# HIVE_BOARD_WIRELESS.net
KiCad netlist of a schematic drawn in Altium Designer
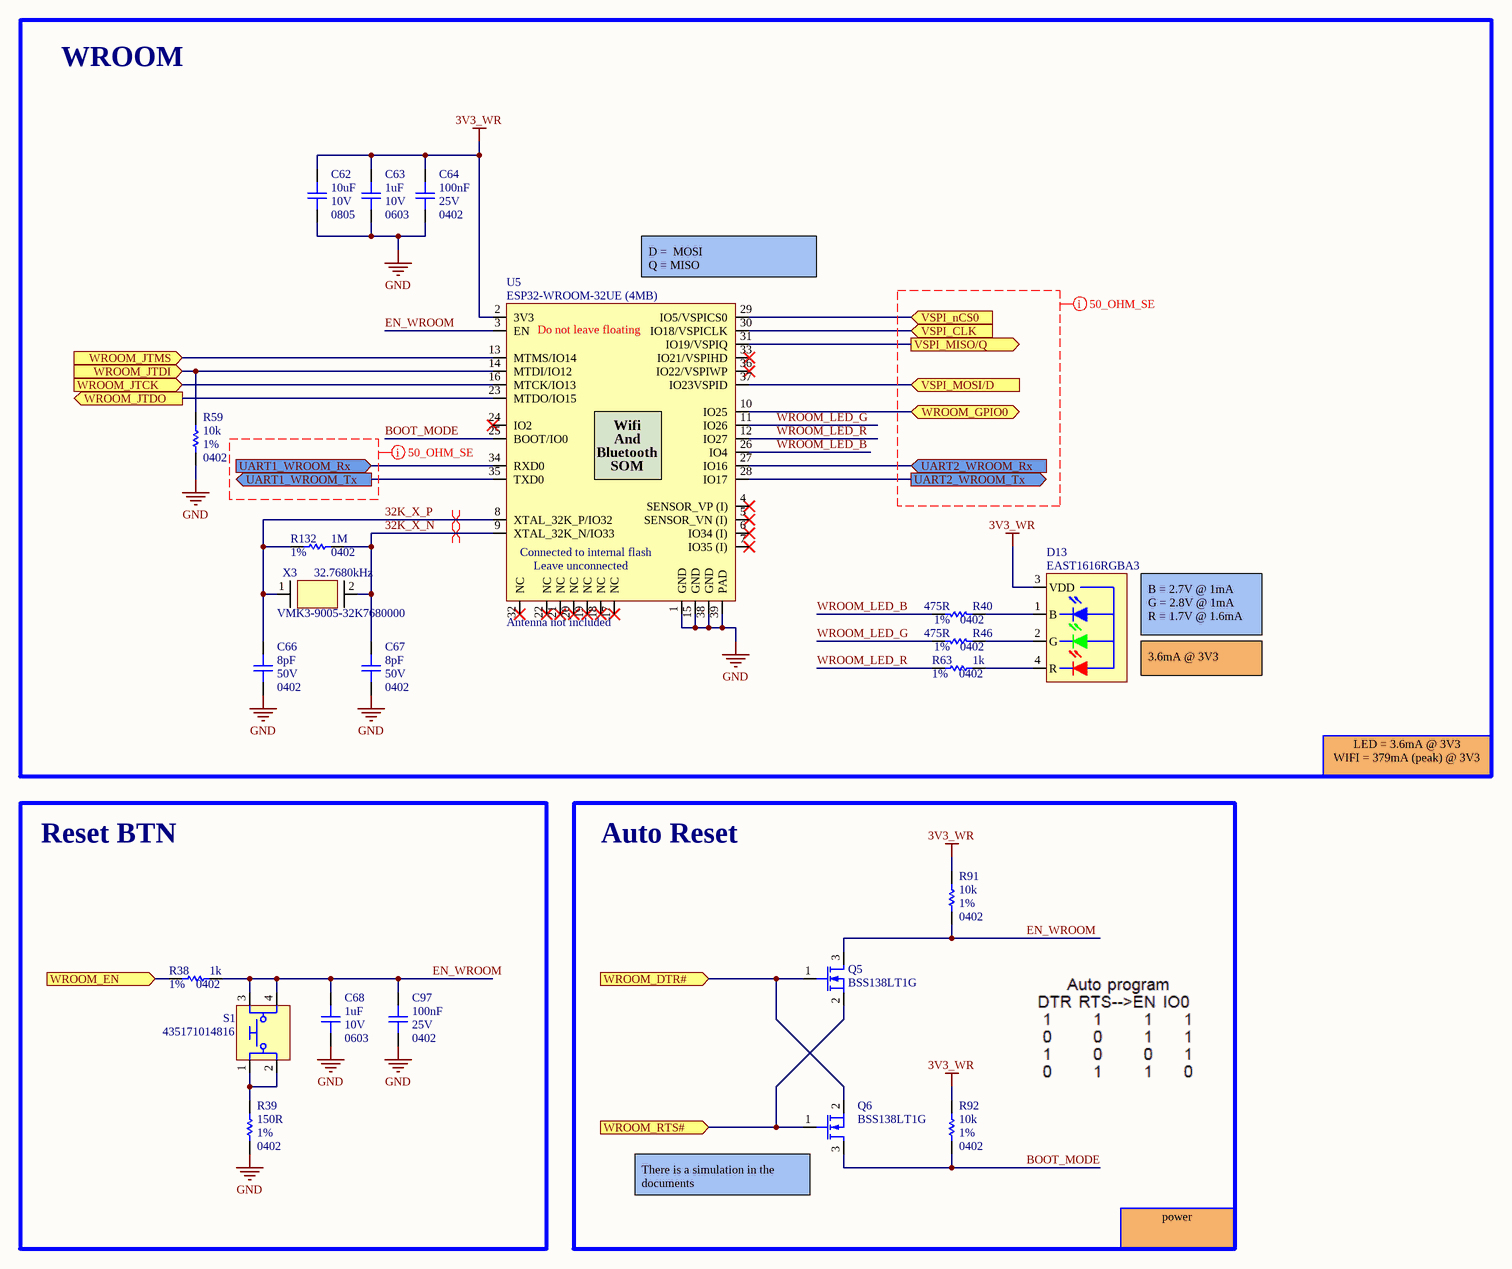
[diagram p0: HIVE_BOARD_WIRELESS.SchDoc]

(export (version "E")
  (design (tool "Eeschema 10.0.6"))
  (components
    (comp (ref "C62")
      (value "10uF")
      (footprint "CAP_CER_0805")
      (description "CAP - CER 10UF 10% 10V X5R - 0805")
      (fields
        (field (name "TOLERANCE") "10%")
        (field (name "PACKAGE") "0805")
        (field (name "VOLTAGE RATING") "10V")
        (field (name "Comment") "LMK212BJ106KG-T")
        (field (name "CREATEDBY/DATE") "Caroline Paulin / 25 juillet 2018")
        (field (name "VERIFIEDBY") "Nicolas V. (2019-01-22)")
      )
      (libsource (lib "GRAMS_MASTER_LIB") (part "CAP_CER_LMK212BJ106KG-T"))
    )
    (comp (ref "C63")
      (value "1uF")
      (footprint "CAP_CER_0603")
      (description "CAP - CER 1uF 10V 10% X5R - 0603")
      (fields
        (field (name "TOLERANCE") "10%")
        (field (name "PACKAGE") "0603")
        (field (name "VOLTAGE RATING") "10V")
        (field (name "Comment") "C0603C105K8PACTU")
        (field (name "CREATEDBY/DATE") "Hubert Dube - 21/07/20")
        (field (name "VERIFIEDBY") "Louis-Daniel Gaulin - 21/07/20")
      )
      (libsource (lib "SWARMUS_LIB") (part "CAP_CER_C0603C105K8PACTU"))
    )
    (comp (ref "C64")
      (value "100nF")
      (footprint "CAP_CER_0402")
      (description "CAP - CER 0.1µF 10% 25V X7R - 0402")
      (fields
        (field (name "TOLERANCE") "10%")
        (field (name "PACKAGE") "0402")
        (field (name "VOLTAGE RATING") "25V")
        (field (name "Comment") "CGA2B3X7R1E104K050BB")
        (field (name "CREATEDBY/DATE") "Nicolas Roy 2018-11-07")
        (field (name "VERIFIEDBY") "Nicolas V. (2019-01-22)")
      )
      (libsource (lib "GRAMS_MASTER_LIB") (part "CAP_CER_CGA2B3X7R1E104K050BB"))
    )
    (comp (ref "C66")
      (value "8pF")
      (footprint "CAP_CER_0402")
      (description "CAP - CER 8PF 50V C0G/NP0 - 0402")
      (fields
        (field (name "TOLERANCE") "±0.5pF")
        (field (name "PACKAGE") "0402")
        (field (name "VOLTAGE RATING") "50V")
        (field (name "Comment") "CC0402DRNPO9BN8R0")
        (field (name "CREATEDBY/DATE") "Hubert Dube - 04/10/20")
        (field (name "VERIFIEDBY") "Louis-Daniel Gaulin - 09/11/2020")
      )
      (libsource (lib "SWARMUS_LIB") (part "CAP_CER_CC0402DRNPO9BN8R0"))
    )
    (comp (ref "C67")
      (value "8pF")
      (footprint "CAP_CER_0402")
      (description "CAP - CER 8PF 50V C0G/NP0 - 0402")
      (fields
        (field (name "TOLERANCE") "±0.5pF")
        (field (name "PACKAGE") "0402")
        (field (name "VOLTAGE RATING") "50V")
        (field (name "Comment") "CC0402DRNPO9BN8R0")
        (field (name "CREATEDBY/DATE") "Hubert Dube - 04/10/20")
        (field (name "VERIFIEDBY") "Louis-Daniel Gaulin - 09/11/2020")
      )
      (libsource (lib "SWARMUS_LIB") (part "CAP_CER_CC0402DRNPO9BN8R0"))
    )
    (comp (ref "C68")
      (value "1uF")
      (footprint "CAP_CER_0603")
      (description "CAP - CER 1uF 10V 10% X5R - 0603")
      (fields
        (field (name "TOLERANCE") "10%")
        (field (name "PACKAGE") "0603")
        (field (name "VOLTAGE RATING") "10V")
        (field (name "Comment") "C0603C105K8PACTU")
        (field (name "CREATEDBY/DATE") "Hubert Dube - 21/07/20")
        (field (name "VERIFIEDBY") "Louis-Daniel Gaulin - 21/07/20")
      )
      (libsource (lib "SWARMUS_LIB") (part "CAP_CER_C0603C105K8PACTU"))
    )
    (comp (ref "C97")
      (value "100nF")
      (footprint "CAP_CER_0402")
      (description "CAP - CER 0.1µF 10% 25V X7R - 0402")
      (fields
        (field (name "TOLERANCE") "10%")
        (field (name "PACKAGE") "0402")
        (field (name "VOLTAGE RATING") "25V")
        (field (name "Comment") "CGA2B3X7R1E104K050BB")
        (field (name "CREATEDBY/DATE") "Nicolas Roy 2018-11-07")
        (field (name "VERIFIEDBY") "Nicolas V. (2019-01-22)")
      )
      (libsource (lib "GRAMS_MASTER_LIB") (part "CAP_CER_CGA2B3X7R1E104K050BB"))
    )
    (comp (ref "D13")
      (value "EAST1616RGBA3")
      (footprint "DIO_EAST1616RGBA3")
      (fields
        (field (name "TOLERANCE") "±50ppm")
        (field (name "CREATEDBY/DATE") "Hubert Dube - 26/02/2021")
        (field (name "VERIFIEDBY") "PA + Hubert Dube - 19/03/2021")
      )
      (libsource (lib "SWARMUS_LIB") (part "DIO_EAST1616RGBA3"))
    )
    (comp (ref "Q5")
      (value "BSS138LT1G")
      (footprint "TRX_NMOS_BSS138LT1G")
      (description "TRX - NMOS - 50V 200MA - SOT−23-3")
      (fields
        (field (name "CREATEDBY/DATE") "Joel Lemay 2018-06-15")
        (field (name "VERIFIEDBY") "Caroline Paulin - 6 sept 2018")
      )
      (libsource (lib "GRAMS_MASTER_LIB") (part "TRX_NMOS_BSS138LT1G"))
    )
    (comp (ref "Q6")
      (value "BSS138LT1G")
      (footprint "TRX_NMOS_BSS138LT1G")
      (description "TRX - NMOS - 50V 200MA - SOT−23-3")
      (fields
        (field (name "CREATEDBY/DATE") "Joel Lemay 2018-06-15")
        (field (name "VERIFIEDBY") "Caroline Paulin - 6 sept 2018")
      )
      (libsource (lib "GRAMS_MASTER_LIB") (part "TRX_NMOS_BSS138LT1G"))
    )
    (comp (ref "R38")
      (value "1k")
      (footprint "RES_0402")
      (description "RES - 1K OHM 1% 1/16W - 0402")
      (fields
        (field (name "TOLERANCE") "1%")
        (field (name "PACKAGE") "0402")
        (field (name "Comment") "RC0402FR-071KL")
        (field (name "CREATEDBY/DATE") "Jonathan Bouchard 2018-07-05")
        (field (name "VERIFIEDBY") "Arnaud Samson 16-07-18")
      )
      (libsource (lib "GRAMS_MASTER_LIB") (part "RES_RC0402FR-071KL"))
    )
    (comp (ref "R39")
      (value "150R")
      (footprint "RES_0402")
      (description "RES - 150R 1% 1/16W - 0402")
      (fields
        (field (name "TOLERANCE") "1%")
        (field (name "PACKAGE") "0402")
        (field (name "Comment") "RC0402FR-07150RL")
        (field (name "CREATEDBY/DATE") "Jonathan Bouchard 2019-03-25")
        (field (name "VERIFIEDBY") "Nicolas V. (2019-05-02)")
      )
      (libsource (lib "GRAMS_MASTER_LIB") (part "RES_RC0402FR-07150RL"))
    )
    (comp (ref "R40")
      (value "475R")
      (footprint "RES_0402")
      (description "RES - 475R 1% 1/10W- 0402")
      (fields
        (field (name "TOLERANCE") "1%")
        (field (name "PACKAGE") "0402")
        (field (name "Comment") "ERJ-2RKF4750X")
        (field (name "CREATEDBY/DATE") "Keven Deslandes 2018-10-17")
        (field (name "VERIFIEDBY") "Carolilne Paulin - 18/12/2018")
      )
      (libsource (lib "GRAMS_MASTER_LIB") (part "RES_ERJ-2RKF4750X"))
    )
    (comp (ref "R46")
      (value "475R")
      (footprint "RES_0402")
      (description "RES - 475R 1% 1/10W- 0402")
      (fields
        (field (name "TOLERANCE") "1%")
        (field (name "PACKAGE") "0402")
        (field (name "Comment") "ERJ-2RKF4750X")
        (field (name "CREATEDBY/DATE") "Keven Deslandes 2018-10-17")
        (field (name "VERIFIEDBY") "Carolilne Paulin - 18/12/2018")
      )
      (libsource (lib "GRAMS_MASTER_LIB") (part "RES_ERJ-2RKF4750X"))
    )
    (comp (ref "R59")
      (value "10k")
      (footprint "RES_0402")
      (description "RES - 10K OHMS 1% 1/16W - 0402")
      (fields
        (field (name "TOLERANCE") "1%")
        (field (name "PACKAGE") "0402")
        (field (name "Comment") "RC0402FR-0710KL")
        (field (name "CREATEDBY/DATE") "Nicolas V. (2018-11-20)")
        (field (name "VERIFIEDBY") "Nicolas V. (2018-11-20)")
      )
      (libsource (lib "GRAMS_MASTER_LIB") (part "RES_RC0402FR-0710KL"))
    )
    (comp (ref "R63")
      (value "1k")
      (footprint "RES_0402")
      (description "RES - 1K OHM 1% 1/16W - 0402")
      (fields
        (field (name "TOLERANCE") "1%")
        (field (name "PACKAGE") "0402")
        (field (name "Comment") "RC0402FR-071KL")
        (field (name "CREATEDBY/DATE") "Jonathan Bouchard 2018-07-05")
        (field (name "VERIFIEDBY") "Arnaud Samson 16-07-18")
      )
      (libsource (lib "GRAMS_MASTER_LIB") (part "RES_RC0402FR-071KL"))
    )
    (comp (ref "R91")
      (value "10k")
      (footprint "RES_0402")
      (description "RES - 10K OHMS 1% 1/16W - 0402")
      (fields
        (field (name "TOLERANCE") "1%")
        (field (name "PACKAGE") "0402")
        (field (name "Comment") "RC0402FR-0710KL")
        (field (name "CREATEDBY/DATE") "Nicolas V. (2018-11-20)")
        (field (name "VERIFIEDBY") "Nicolas V. (2018-11-20)")
      )
      (libsource (lib "GRAMS_MASTER_LIB") (part "RES_RC0402FR-0710KL"))
    )
    (comp (ref "R92")
      (value "10k")
      (footprint "RES_0402")
      (description "RES - 10K OHMS 1% 1/16W - 0402")
      (fields
        (field (name "TOLERANCE") "1%")
        (field (name "PACKAGE") "0402")
        (field (name "Comment") "RC0402FR-0710KL")
        (field (name "CREATEDBY/DATE") "Nicolas V. (2018-11-20)")
        (field (name "VERIFIEDBY") "Nicolas V. (2018-11-20)")
      )
      (libsource (lib "GRAMS_MASTER_LIB") (part "RES_RC0402FR-0710KL"))
    )
    (comp (ref "R132")
      (value "1M")
      (footprint "RES_0402")
      (description "RES - 1M 1% 1/16W - 0402")
      (fields
        (field (name "TOLERANCE") "1%")
        (field (name "PACKAGE") "0402")
        (field (name "Comment") "RC0402FR-071ML")
        (field (name "CREATEDBY/DATE") "Keven Deslandes 2018-11-09")
        (field (name "VERIFIEDBY") "Caroline Paulin - 7 janv 2019")
      )
      (libsource (lib "GRAMS_MASTER_LIB") (part "RES_RC0402FR-071ML"))
    )
    (comp (ref "S1")
      (value "435171014816")
      (footprint "SWI_TACT_435171014816")
      (description "SWI - SWITCH TACTILE SPST-NO 0.05A 12V -SMD")
      (fields
        (field (name "CREATEDBY/DATE") "Hubert Dube - 22/07/20")
        (field (name "VERIFIEDBY") "Louis-Daniel Gaulin / 12-11-2020")
      )
      (libsource (lib "SWARMUS_LIB") (part "SWI_TACT_435171014816"))
    )
    (comp (ref "U5")
      (value "ESP32-WROOM-32UE (4MB)")
      (footprint "COM_ESP32-WROOM-32UE(8MB)")
      (fields
        (field (name "NOTE") "Antenna not included")
        (field (name "VERIFIEDBY") "Philippe Arsenault/ 2021-03-11")
        (field (name "CREATEDBY/DATE") "Hubert Dube -  25/02/2021")
      )
      (libsource (lib "SWARMUS_LIB") (part "COM_ESP32-WROOM-32UE(4MB)"))
    )
    (comp (ref "X3")
      (value "VMK3-9005-32K7680000")
      (footprint "CRY_VMK3-9005-32K7680000")
      (description "CRY - 32.768KHZ tol:20ppm  - 2-SMD")
      (fields
        (field (name "TOLERANCE") "±20ppm")
        (field (name "ALTIUM_VALUE") "32.7680kHz")
        (field (name "CREATEDBY/DATE") "Louis-Daniel Gaulin / 08-04-2021")
        (field (name "VERIFIEDBY") "Philippe Arsenault/2021-04-15")
      )
      (libsource (lib "SWARMUS_LIB") (part "CRY_VMK3-9005-32K7680000"))
    )
  )
  (nets
    (net (code "1") (name "/32K_X_N") (class "Default")
      (node (ref "C67") (pin "2") (pinfunction "2_2") (pintype "passive"))
      (node (ref "R132") (pin "1") (pinfunction "1_1") (pintype "passive"))
      (node (ref "U5") (pin "9") (pinfunction "XTAL_32K_N/IO33_9") (pintype "passive"))
      (node (ref "X3") (pin "2") (pinfunction "Out/In_2") (pintype "passive"))
    )
    (net (code "2") (name "/32K_X_P") (class "Default")
      (node (ref "C66") (pin "2") (pinfunction "2_2") (pintype "passive"))
      (node (ref "R132") (pin "2") (pinfunction "2_2") (pintype "passive"))
      (node (ref "U5") (pin "8") (pinfunction "XTAL_32K_P/IO32_8") (pintype "passive"))
      (node (ref "X3") (pin "1") (pinfunction "In/Out_1") (pintype "passive"))
    )
    (net (code "3") (name "/BOOT_MODE") (class "Default")
      (node (ref "Q6") (pin "3") (pinfunction "D_3") (pintype "passive"))
      (node (ref "R92") (pin "1") (pinfunction "1_1") (pintype "passive"))
      (node (ref "U5") (pin "25") (pinfunction "BOOT/IO0_25") (pintype "passive"))
    )
    (net (code "4") (name "/EN_WROOM") (class "Default")
      (node (ref "C68") (pin "1") (pinfunction "1_1") (pintype "passive"))
      (node (ref "C97") (pin "2") (pinfunction "2_2") (pintype "passive"))
      (node (ref "Q5") (pin "3") (pinfunction "D_3") (pintype "passive"))
      (node (ref "R38") (pin "1") (pinfunction "1_1") (pintype "passive"))
      (node (ref "R91") (pin "1") (pinfunction "1_1") (pintype "passive"))
      (node (ref "S1") (pin "3") (pinfunction "3_3") (pintype "passive"))
      (node (ref "S1") (pin "4") (pinfunction "4_4") (pintype "passive"))
      (node (ref "U5") (pin "3") (pinfunction "EN_3") (pintype "passive"))
    )
    (net (code "5") (name "/UART1_WROOM_Rx") (class "Default")
      (node (ref "U5") (pin "34") (pinfunction "RXD0_34") (pintype "passive"))
    )
    (net (code "6") (name "/UART1_WROOM_Tx") (class "Default")
      (node (ref "U5") (pin "35") (pinfunction "TXD0_35") (pintype "passive"))
    )
    (net (code "7") (name "/UART2_WROOM_Rx") (class "Default")
      (node (ref "U5") (pin "27") (pinfunction "IO16_27") (pintype "passive"))
    )
    (net (code "8") (name "/UART2_WROOM_Tx") (class "Default")
      (node (ref "U5") (pin "28") (pinfunction "IO17_28") (pintype "passive"))
    )
    (net (code "9") (name "/VSPI_CLK") (class "Default")
      (node (ref "U5") (pin "30") (pinfunction "IO18/VSPICLK_30") (pintype "passive"))
    )
    (net (code "10") (name "/VSPI_MISO{slash}Q") (class "Default")
      (node (ref "U5") (pin "31") (pinfunction "IO19/VSPIQ_31") (pintype "passive"))
    )
    (net (code "11") (name "/VSPI_MOSI{slash}D") (class "Default")
      (node (ref "U5") (pin "37") (pinfunction "IO23VSPID_37") (pintype "passive"))
    )
    (net (code "12") (name "/VSPI_nCS0") (class "Default")
      (node (ref "U5") (pin "29") (pinfunction "IO5/VSPICS0_29") (pintype "passive"))
    )
    (net (code "13") (name "/WROOM_DTR#") (class "Default")
      (node (ref "Q5") (pin "1") (pinfunction "G_1") (pintype "passive"))
      (node (ref "Q6") (pin "2") (pinfunction "S_2") (pintype "passive"))
    )
    (net (code "14") (name "/WROOM_EN") (class "Default")
      (node (ref "R38") (pin "2") (pinfunction "2_2") (pintype "passive"))
    )
    (net (code "15") (name "/WROOM_GPIO0") (class "Default")
      (node (ref "U5") (pin "10") (pinfunction "IO25_10") (pintype "passive"))
    )
    (net (code "16") (name "/WROOM_JTCK") (class "Default")
      (node (ref "U5") (pin "16") (pinfunction "MTCK/IO13_16") (pintype "passive"))
    )
    (net (code "17") (name "/WROOM_JTDI") (class "Default")
      (node (ref "R59") (pin "2") (pinfunction "2_2") (pintype "passive"))
      (node (ref "U5") (pin "14") (pinfunction "MTDI/IO12_14") (pintype "passive"))
    )
    (net (code "18") (name "/WROOM_JTDO") (class "Default")
      (node (ref "U5") (pin "23") (pinfunction "MTDO/IO15_23") (pintype "passive"))
    )
    (net (code "19") (name "/WROOM_JTMS") (class "Default")
      (node (ref "U5") (pin "13") (pinfunction "MTMS/IO14_13") (pintype "passive"))
    )
    (net (code "20") (name "/WROOM_LED_B") (class "Default")
      (node (ref "R40") (pin "2") (pinfunction "2_2") (pintype "passive"))
      (node (ref "U5") (pin "26") (pinfunction "IO4_26") (pintype "passive"))
    )
    (net (code "21") (name "/WROOM_LED_G") (class "Default")
      (node (ref "R46") (pin "2") (pinfunction "2_2") (pintype "passive"))
      (node (ref "U5") (pin "11") (pinfunction "IO26_11") (pintype "passive"))
    )
    (net (code "22") (name "/WROOM_LED_R") (class "Default")
      (node (ref "R63") (pin "2") (pinfunction "2_2") (pintype "passive"))
      (node (ref "U5") (pin "12") (pinfunction "IO27_12") (pintype "passive"))
    )
    (net (code "23") (name "/WROOM_RTS#") (class "Default")
      (node (ref "Q5") (pin "2") (pinfunction "S_2") (pintype "passive"))
      (node (ref "Q6") (pin "1") (pinfunction "G_1") (pintype "passive"))
    )
    (net (code "24") (name "3V3_WR") (class "Default")
      (node (ref "C62") (pin "2") (pinfunction "2_2") (pintype "passive"))
      (node (ref "C63") (pin "1") (pinfunction "1_1") (pintype "passive"))
      (node (ref "C64") (pin "2") (pinfunction "2_2") (pintype "passive"))
      (node (ref "D13") (pin "3") (pinfunction "VDD_3") (pintype "passive"))
      (node (ref "R91") (pin "2") (pinfunction "2_2") (pintype "passive"))
      (node (ref "R92") (pin "2") (pinfunction "2_2") (pintype "passive"))
      (node (ref "U5") (pin "2") (pinfunction "3V3_2") (pintype "passive"))
    )
    (net (code "25") (name "GND") (class "Default")
      (node (ref "C62") (pin "1") (pinfunction "1_1") (pintype "passive"))
      (node (ref "C63") (pin "2") (pinfunction "2_2") (pintype "passive"))
      (node (ref "C64") (pin "1") (pinfunction "1_1") (pintype "passive"))
      (node (ref "C66") (pin "1") (pinfunction "1_1") (pintype "passive"))
      (node (ref "C67") (pin "1") (pinfunction "1_1") (pintype "passive"))
      (node (ref "C68") (pin "2") (pinfunction "2_2") (pintype "passive"))
      (node (ref "C97") (pin "1") (pinfunction "1_1") (pintype "passive"))
      (node (ref "R39") (pin "1") (pinfunction "1_1") (pintype "passive"))
      (node (ref "R59") (pin "1") (pinfunction "1_1") (pintype "passive"))
      (node (ref "U5") (pin "1") (pinfunction "GND_1") (pintype "passive"))
      (node (ref "U5") (pin "15") (pinfunction "GND_15") (pintype "passive"))
      (node (ref "U5") (pin "38") (pinfunction "GND_38") (pintype "passive"))
      (node (ref "U5") (pin "39") (pinfunction "PAD_39") (pintype "passive"))
    )
    (net (code "26") (name "Net-(D13-B)") (class "Default")
      (node (ref "D13") (pin "1") (pinfunction "B_1") (pintype "passive"))
      (node (ref "R40") (pin "1") (pinfunction "1_1") (pintype "passive"))
    )
    (net (code "27") (name "Net-(D13-G)") (class "Default")
      (node (ref "D13") (pin "2") (pinfunction "G_2") (pintype "passive"))
      (node (ref "R46") (pin "1") (pinfunction "1_1") (pintype "passive"))
    )
    (net (code "28") (name "Net-(D13-R)") (class "Default")
      (node (ref "D13") (pin "4") (pinfunction "R_4") (pintype "passive"))
      (node (ref "R63") (pin "1") (pinfunction "1_1") (pintype "passive"))
    )
    (net (code "29") (name "Net-(R39-Pad2)") (class "Default")
      (node (ref "R39") (pin "2") (pinfunction "2_2") (pintype "passive"))
      (node (ref "S1") (pin "1") (pinfunction "1_1") (pintype "passive"))
      (node (ref "S1") (pin "2") (pinfunction "2_2") (pintype "passive"))
    )
    (net (code "30") (name "unconnected-(U5-IO2-Pad24)") (class "Default")
      (node (ref "U5") (pin "24") (pinfunction "IO2_24") (pintype "passive+no_connect"))
    )
    (net (code "31") (name "unconnected-(U5-IO21{slash}VSPIHD-Pad33)") (class "Default")
      (node (ref "U5") (pin "33") (pinfunction "IO21/VSPIHD_33") (pintype "passive+no_connect"))
    )
    (net (code "32") (name "unconnected-(U5-IO22{slash}VSPIWP-Pad36)") (class "Default")
      (node (ref "U5") (pin "36") (pinfunction "IO22/VSPIWP_36") (pintype "passive+no_connect"))
    )
    (net (code "33") (name "unconnected-(U5-IO34_(I)-Pad6)") (class "Default")
      (node (ref "U5") (pin "6") (pinfunction "IO34_(I)_6") (pintype "passive+no_connect"))
    )
    (net (code "34") (name "unconnected-(U5-IO35_(I)-Pad7)") (class "Default")
      (node (ref "U5") (pin "7") (pinfunction "IO35_(I)_7") (pintype "passive+no_connect"))
    )
    (net (code "35") (name "unconnected-(U5-NC-Pad17)") (class "Default")
      (node (ref "U5") (pin "17") (pinfunction "NC_17") (pintype "passive+no_connect"))
    )
    (net (code "36") (name "unconnected-(U5-NC-Pad18)") (class "Default")
      (node (ref "U5") (pin "18") (pinfunction "NC_18") (pintype "passive+no_connect"))
    )
    (net (code "37") (name "unconnected-(U5-NC-Pad19)") (class "Default")
      (node (ref "U5") (pin "19") (pinfunction "NC_19") (pintype "passive+no_connect"))
    )
    (net (code "38") (name "unconnected-(U5-NC-Pad20)") (class "Default")
      (node (ref "U5") (pin "20") (pinfunction "NC_20") (pintype "passive+no_connect"))
    )
    (net (code "39") (name "unconnected-(U5-NC-Pad21)") (class "Default")
      (node (ref "U5") (pin "21") (pinfunction "NC_21") (pintype "passive+no_connect"))
    )
    (net (code "40") (name "unconnected-(U5-NC-Pad22)") (class "Default")
      (node (ref "U5") (pin "22") (pinfunction "NC_22") (pintype "passive+no_connect"))
    )
    (net (code "41") (name "unconnected-(U5-NC-Pad32)") (class "Default")
      (node (ref "U5") (pin "32") (pinfunction "NC_32") (pintype "passive+no_connect"))
    )
    (net (code "42") (name "unconnected-(U5-SENSOR_VN_(I)-Pad5)") (class "Default")
      (node (ref "U5") (pin "5") (pinfunction "SENSOR_VN_(I)_5") (pintype "passive+no_connect"))
    )
    (net (code "43") (name "unconnected-(U5-SENSOR_VP_(I)-Pad4)") (class "Default")
      (node (ref "U5") (pin "4") (pinfunction "SENSOR_VP_(I)_4") (pintype "passive+no_connect"))
    )
  )
)
